# DriverModule.net
KiCad netlist of a schematic drawn in EAGLE
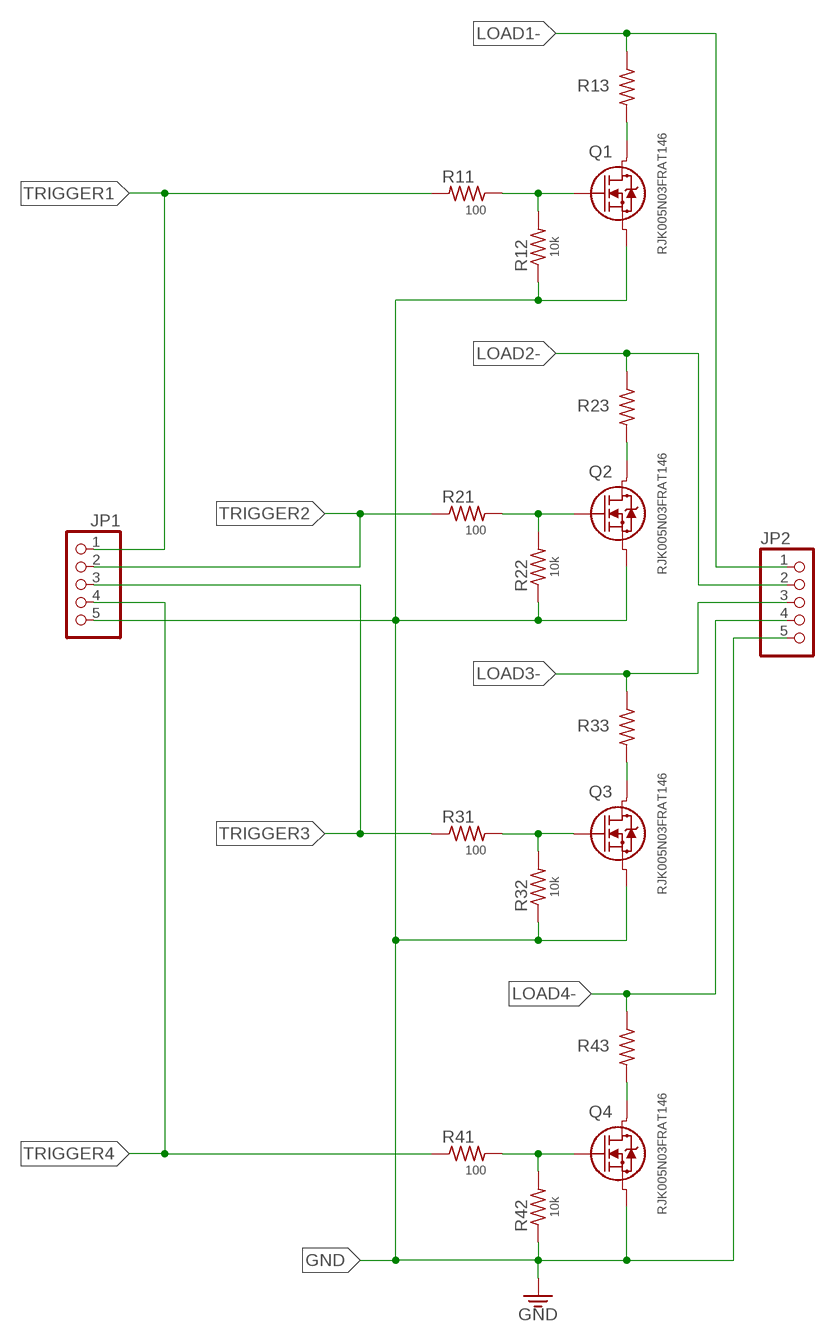
[diagram p0: schematic, sheet 1]

(export (version "E")
  (design (tool "Eeschema 10.0.6"))
  (components
    (comp (ref "JP1")
      (value "HEADER-1X576MIL")
      (footprint "eagle-import:1X05_ROUND_76")
      (libsource (lib "eagle-import") (part "HEADER-1X576MIL"))
    )
    (comp (ref "JP2")
      (value "HEADER-1X576MIL")
      (footprint "eagle-import:1X05_ROUND_76")
      (libsource (lib "eagle-import") (part "HEADER-1X576MIL"))
    )
    (comp (ref "Q1")
      (value "RJK005N03FRAT146")
      (footprint "eagle-import:TRANS_RHK003N_ROM-M")
      (fields (field (name "COPYRIGHT") "Copyright (C) 2022 Ultra Librarian. All rights reserved."))
      (libsource (lib "eagle-import") (part "RJK005N03FRAT146TRANS_RHK003N_ROM-M"))
    )
    (comp (ref "Q2")
      (value "RJK005N03FRAT146")
      (footprint "eagle-import:TRANS_RHK003N_ROM-M")
      (fields (field (name "COPYRIGHT") "Copyright (C) 2022 Ultra Librarian. All rights reserved."))
      (libsource (lib "eagle-import") (part "RJK005N03FRAT146TRANS_RHK003N_ROM-M"))
    )
    (comp (ref "Q3")
      (value "RJK005N03FRAT146")
      (footprint "eagle-import:TRANS_RHK003N_ROM-M")
      (fields (field (name "COPYRIGHT") "Copyright (C) 2022 Ultra Librarian. All rights reserved."))
      (libsource (lib "eagle-import") (part "RJK005N03FRAT146TRANS_RHK003N_ROM-M"))
    )
    (comp (ref "Q4")
      (value "RJK005N03FRAT146")
      (footprint "eagle-import:TRANS_RHK003N_ROM-M")
      (fields (field (name "COPYRIGHT") "Copyright (C) 2022 Ultra Librarian. All rights reserved."))
      (libsource (lib "eagle-import") (part "RJK005N03FRAT146TRANS_RHK003N_ROM-M"))
    )
    (comp (ref "R11")
      (value "100")
      (footprint "eagle-import:R0603")
      (libsource (lib "eagle-import") (part "R-US_R0603"))
    )
    (comp (ref "R12")
      (value "10k")
      (footprint "eagle-import:R0603")
      (libsource (lib "eagle-import") (part "R-US_R0603"))
    )
    (comp (ref "R13")
      (value "R-US_R1206")
      (footprint "eagle-import:R1206")
      (libsource (lib "eagle-import") (part "R-US_R1206"))
    )
    (comp (ref "R21")
      (value "100")
      (footprint "eagle-import:R0603")
      (libsource (lib "eagle-import") (part "R-US_R0603"))
    )
    (comp (ref "R22")
      (value "10k")
      (footprint "eagle-import:R0603")
      (libsource (lib "eagle-import") (part "R-US_R0603"))
    )
    (comp (ref "R23")
      (value "R-US_R1206")
      (footprint "eagle-import:R1206")
      (libsource (lib "eagle-import") (part "R-US_R1206"))
    )
    (comp (ref "R31")
      (value "100")
      (footprint "eagle-import:R0603")
      (libsource (lib "eagle-import") (part "R-US_R0603"))
    )
    (comp (ref "R32")
      (value "10k")
      (footprint "eagle-import:R0603")
      (libsource (lib "eagle-import") (part "R-US_R0603"))
    )
    (comp (ref "R33")
      (value "R-US_R1206")
      (footprint "eagle-import:R1206")
      (libsource (lib "eagle-import") (part "R-US_R1206"))
    )
    (comp (ref "R41")
      (value "100")
      (footprint "eagle-import:R0603")
      (libsource (lib "eagle-import") (part "R-US_R0603"))
    )
    (comp (ref "R42")
      (value "10k")
      (footprint "eagle-import:R0603")
      (libsource (lib "eagle-import") (part "R-US_R0603"))
    )
    (comp (ref "R43")
      (value "R-US_R1206")
      (footprint "eagle-import:R1206")
      (libsource (lib "eagle-import") (part "R-US_R1206"))
    )
  )
  (nets
    (net (code "1") (name "GND") (class "Default")
      (node (ref "JP1") (pin "5") (pinfunction "5_5") (pintype "passive"))
      (node (ref "JP2") (pin "5") (pinfunction "5_5") (pintype "passive"))
      (node (ref "Q1") (pin "3") (pinfunction "3_3") (pintype "passive"))
      (node (ref "Q2") (pin "3") (pinfunction "3_3") (pintype "passive"))
      (node (ref "Q3") (pin "3") (pinfunction "3_3") (pintype "passive"))
      (node (ref "Q4") (pin "3") (pinfunction "3_3") (pintype "passive"))
      (node (ref "R12") (pin "1") (pinfunction "1_1") (pintype "passive"))
      (node (ref "R22") (pin "1") (pinfunction "1_1") (pintype "passive"))
      (node (ref "R32") (pin "1") (pinfunction "1_1") (pintype "passive"))
      (node (ref "R42") (pin "1") (pinfunction "1_1") (pintype "passive"))
    )
    (net (code "2") (name "LOAD1-") (class "Default")
      (node (ref "JP2") (pin "1") (pinfunction "1_1") (pintype "passive"))
      (node (ref "R13") (pin "1") (pinfunction "1_1") (pintype "passive"))
    )
    (net (code "3") (name "LOAD2-") (class "Default")
      (node (ref "JP2") (pin "2") (pinfunction "2_2") (pintype "passive"))
      (node (ref "R23") (pin "1") (pinfunction "1_1") (pintype "passive"))
    )
    (net (code "4") (name "LOAD3-") (class "Default")
      (node (ref "JP2") (pin "3") (pinfunction "3_3") (pintype "passive"))
      (node (ref "R33") (pin "1") (pinfunction "1_1") (pintype "passive"))
    )
    (net (code "5") (name "LOAD4-") (class "Default")
      (node (ref "JP2") (pin "4") (pinfunction "4_4") (pintype "passive"))
      (node (ref "R43") (pin "1") (pinfunction "1_1") (pintype "passive"))
    )
    (net (code "6") (name "Net-(Q1-1)") (class "Default")
      (node (ref "Q1") (pin "2") (pinfunction "1_2") (pintype "passive"))
      (node (ref "R11") (pin "1") (pinfunction "1_1") (pintype "passive"))
      (node (ref "R12") (pin "2") (pinfunction "2_2") (pintype "passive"))
    )
    (net (code "7") (name "Net-(Q1-2)") (class "Default")
      (node (ref "Q1") (pin "1") (pinfunction "2_1") (pintype "passive"))
      (node (ref "R13") (pin "2") (pinfunction "2_2") (pintype "passive"))
    )
    (net (code "8") (name "Net-(Q2-1)") (class "Default")
      (node (ref "Q2") (pin "2") (pinfunction "1_2") (pintype "passive"))
      (node (ref "R21") (pin "2") (pinfunction "2_2") (pintype "passive"))
      (node (ref "R22") (pin "2") (pinfunction "2_2") (pintype "passive"))
    )
    (net (code "9") (name "Net-(Q2-2)") (class "Default")
      (node (ref "Q2") (pin "1") (pinfunction "2_1") (pintype "passive"))
      (node (ref "R23") (pin "2") (pinfunction "2_2") (pintype "passive"))
    )
    (net (code "10") (name "Net-(Q3-1)") (class "Default")
      (node (ref "Q3") (pin "2") (pinfunction "1_2") (pintype "passive"))
      (node (ref "R31") (pin "2") (pinfunction "2_2") (pintype "passive"))
      (node (ref "R32") (pin "2") (pinfunction "2_2") (pintype "passive"))
    )
    (net (code "11") (name "Net-(Q3-2)") (class "Default")
      (node (ref "Q3") (pin "1") (pinfunction "2_1") (pintype "passive"))
      (node (ref "R33") (pin "2") (pinfunction "2_2") (pintype "passive"))
    )
    (net (code "12") (name "Net-(Q4-1)") (class "Default")
      (node (ref "Q4") (pin "2") (pinfunction "1_2") (pintype "passive"))
      (node (ref "R41") (pin "2") (pinfunction "2_2") (pintype "passive"))
      (node (ref "R42") (pin "2") (pinfunction "2_2") (pintype "passive"))
    )
    (net (code "13") (name "Net-(Q4-2)") (class "Default")
      (node (ref "Q4") (pin "1") (pinfunction "2_1") (pintype "passive"))
      (node (ref "R43") (pin "2") (pinfunction "2_2") (pintype "passive"))
    )
    (net (code "14") (name "TRIGGER1") (class "Default")
      (node (ref "JP1") (pin "1") (pinfunction "1_1") (pintype "passive"))
      (node (ref "R11") (pin "2") (pinfunction "2_2") (pintype "passive"))
    )
    (net (code "15") (name "TRIGGER2") (class "Default")
      (node (ref "JP1") (pin "2") (pinfunction "2_2") (pintype "passive"))
      (node (ref "R21") (pin "1") (pinfunction "1_1") (pintype "passive"))
    )
    (net (code "16") (name "TRIGGER3") (class "Default")
      (node (ref "JP1") (pin "3") (pinfunction "3_3") (pintype "passive"))
      (node (ref "R31") (pin "1") (pinfunction "1_1") (pintype "passive"))
    )
    (net (code "17") (name "TRIGGER4") (class "Default")
      (node (ref "JP1") (pin "4") (pinfunction "4_4") (pintype "passive"))
      (node (ref "R41") (pin "1") (pinfunction "1_1") (pintype "passive"))
    )
  )
)
